# Eth-Crystal.net
KiCad netlist of a schematic drawn in Altium Designer
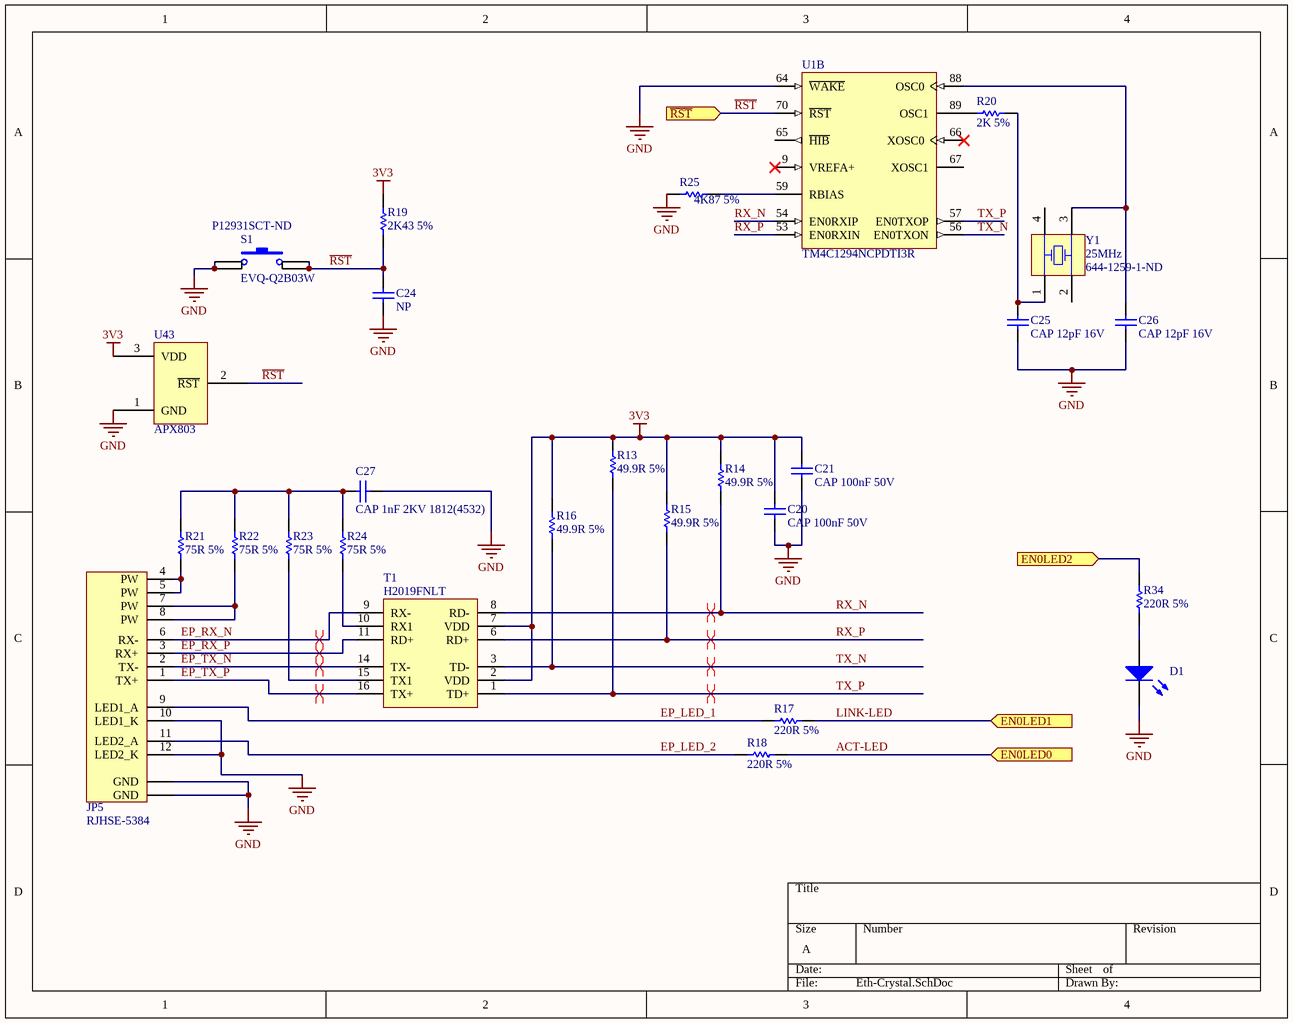
[diagram p0: Eth-Crystal.SchDoc]

(export (version "E")
  (design (tool "Eeschema 10.0.6"))
  (components
    (comp (ref "C20")
      (value "CAP 100nF 50V")
      (footprint "CAPC0603(1608)100_M")
      (description "CAP 100nF 50V Â±0.1pF 0603 (1608 Metric) Thickness 1mm SMD")
      (fields (field (name "TOLERANCE") "Â±0.1pF"))
      (libsource (lib "Altium Content Vault") (part "CMP-1035-00010-1"))
    )
    (comp (ref "C21")
      (value "CAP 100nF 50V")
      (footprint "CAPC0603(1608)100_M")
      (description "CAP 100nF 50V Â±0.1pF 0603 (1608 Metric) Thickness 1mm SMD")
      (fields (field (name "TOLERANCE") "Â±0.1pF"))
      (libsource (lib "Altium Content Vault") (part "CMP-1035-00010-1"))
    )
    (comp (ref "C24")
      (value "NP")
      (footprint "0603")
      (description "Capacitor (Semiconductor SIM Model)")
      (fields (field (name "PUBLISHER") "Altium Limited"))
      (libsource (lib "snarc+") (part "Cap_100pF"))
    )
    (comp (ref "C25")
      (value "CAP 12pF 16V")
      (footprint "CAPC0603(1608)100_L")
      (description "CAP 12pF 16V Â±0.25pF 0603 (1608 Metric) Thickness 1mm SMD")
      (fields (field (name "TOLERANCE") "Â±0.25pF"))
      (libsource (lib "Altium Content Vault") (part "CAP"))
    )
    (comp (ref "C26")
      (value "CAP 12pF 16V")
      (footprint "CAPC0603(1608)100_L")
      (description "CAP 12pF 16V Â±0.25pF 0603 (1608 Metric) Thickness 1mm SMD")
      (fields (field (name "TOLERANCE") "Â±0.25pF"))
      (libsource (lib "Altium Content Vault") (part "CAP"))
    )
    (comp (ref "C27")
      (value "CAP 1nF 2KV 1812(4532)")
      (footprint "CAPC1812(4532)230_N")
      (description "CAP 1nF 2KV Â±10% 1812 (4532 Metric) Thickness 2.3mm SMD")
      (fields (field (name "TOLERANCE") "Â±10%"))
      (libsource (lib "Altium Content Vault") (part "CAP"))
    )
    (comp (ref "D1")
      (value "LED")
      (footprint "LED-0603")
      (description "Typical RED, GREEN, YELLOW, AMBER GaAs LED")
      (fields (field (name "PUBLISHER") "Altium Limited"))
      (libsource (lib "HSBNE-Vend") (part "LED"))
    )
    (comp (ref "JP5")
      (value "RJHSE-5384")
      (footprint "RJHSE-5484")
      (description "Ethernet Socket RJ45 With Leds")
      (libsource (lib "snarc+") (part "Ethernet Socket"))
    )
    (comp (ref "R13")
      (value "49.9R 5%")
      (footprint "RESC0603(1608)_M")
      (description "49.9R 0.1W 5% 0603 (1608 Metric)  SMD")
      (fields (field (name "TOLERANCE") "5 %") (field (name "POWER") "0.1 W"))
      (libsource (lib "Altium Content Vault") (part "CMP-1012-00042-1"))
    )
    (comp (ref "R14")
      (value "49.9R 5%")
      (footprint "RESC0603(1608)_M")
      (description "49.9R 0.1W 5% 0603 (1608 Metric)  SMD")
      (fields (field (name "TOLERANCE") "5 %") (field (name "POWER") "0.1 W"))
      (libsource (lib "Altium Content Vault") (part "CMP-1012-00042-1"))
    )
    (comp (ref "R15")
      (value "49.9R 5%")
      (footprint "RESC0603(1608)_M")
      (description "49.9R 0.1W 5% 0603 (1608 Metric)  SMD")
      (fields (field (name "TOLERANCE") "5 %") (field (name "POWER") "0.1 W"))
      (libsource (lib "Altium Content Vault") (part "CMP-1012-00042-1"))
    )
    (comp (ref "R16")
      (value "49.9R 5%")
      (footprint "RESC0603(1608)_M")
      (description "49.9R 0.1W 5% 0603 (1608 Metric)  SMD")
      (fields (field (name "TOLERANCE") "5 %") (field (name "POWER") "0.1 W"))
      (libsource (lib "Altium Content Vault") (part "CMP-1012-00042-1"))
    )
    (comp (ref "R17")
      (value "220R 5%")
      (footprint "RESC0603(1608)_M")
      (description "220R 0.1W 5% 0603 (1608 Metric)  SMD")
      (fields (field (name "POWER") "0.1 W") (field (name "TOLERANCE") "5 %"))
      (libsource (lib "Altium Content Vault") (part "CMP-1012-00058-1"))
    )
    (comp (ref "R18")
      (value "220R 5%")
      (footprint "RESC0603(1608)_M")
      (description "220R 0.1W 5% 0603 (1608 Metric)  SMD")
      (fields (field (name "POWER") "0.1 W") (field (name "TOLERANCE") "5 %"))
      (libsource (lib "Altium Content Vault") (part "CMP-1012-00058-1"))
    )
    (comp (ref "R19")
      (value "2K43 5%")
      (footprint "RESC0603(1608)_M")
      (description "2K43 0.1W 5% 0603 (1608 Metric)  SMD")
      (fields (field (name "TOLERANCE") "5 %") (field (name "POWER") "0.1 W"))
      (libsource (lib "Altium Content Vault") (part "CMP-1012-00083-1"))
    )
    (comp (ref "R20")
      (value "2K 5%")
      (footprint "RESC0603(1608)_N")
      (description "2K 0.1W 5% 0603 (1608 Metric)  SMD")
      (fields (field (name "TOLERANCE") "5 %") (field (name "POWER") "0.1 W"))
      (libsource (lib "Altium Content Vault") (part "RES"))
    )
    (comp (ref "R21")
      (value "75R 5%")
      (footprint "RESC0603(1608)_N")
      (description "75R 0.1W 5% 0603 (1608 Metric)  SMD")
      (fields (field (name "TOLERANCE") "5 %") (field (name "POWER") "0.1 W"))
      (libsource (lib "Altium Content Vault") (part "CMP-1012-00047-1"))
    )
    (comp (ref "R22")
      (value "75R 5%")
      (footprint "RESC0603(1608)_N")
      (description "75R 0.1W 5% 0603 (1608 Metric)  SMD")
      (fields (field (name "TOLERANCE") "5 %") (field (name "POWER") "0.1 W"))
      (libsource (lib "Altium Content Vault") (part "CMP-1012-00047-1"))
    )
    (comp (ref "R23")
      (value "75R 5%")
      (footprint "RESC0603(1608)_N")
      (description "75R 0.1W 5% 0603 (1608 Metric)  SMD")
      (fields (field (name "TOLERANCE") "5 %") (field (name "POWER") "0.1 W"))
      (libsource (lib "Altium Content Vault") (part "CMP-1012-00047-1"))
    )
    (comp (ref "R24")
      (value "75R 5%")
      (footprint "RESC0603(1608)_N")
      (description "75R 0.1W 5% 0603 (1608 Metric)  SMD")
      (fields (field (name "TOLERANCE") "5 %") (field (name "POWER") "0.1 W"))
      (libsource (lib "Altium Content Vault") (part "CMP-1012-00047-1"))
    )
    (comp (ref "R25")
      (value "4K87 5%")
      (footprint "RESC0603(1608)_M")
      (description "4K87 0.1W 5% 0603 (1608 Metric)  SMD")
      (fields (field (name "TOLERANCE") "5 %") (field (name "POWER") "0.1 W"))
      (libsource (lib "Altium Content Vault") (part "CMP-1012-00090-1"))
    )
    (comp (ref "R34")
      (value "220R 5%")
      (footprint "RESC0603(1608)_M")
      (description "220R 0.1W 5% 0603 (1608 Metric)  SMD")
      (fields (field (name "POWER") "0.1 W") (field (name "TOLERANCE") "5 %"))
      (libsource (lib "Altium Content Vault") (part "CMP-1012-00058-1"))
    )
    (comp (ref "S1")
      (value "EVQ-Q2B03W")
      (footprint "TACTILE_SWITCH_SMD")
      (description "Switch")
      (fields
        (field (name "SUPPLIER PART NUMBER 1") "P12931SCT-ND")
        (field (name "PUBLISHER") "Altium Limited")
      )
      (libsource (lib "snarc+") (part "SW-PB"))
    )
    (comp (ref "T1")
      (value "H2019FNLT")
      (footprint "HXXXX")
      (description "Power over Ethernet Magnetic Module")
      (fields (field (name "PUBLISHER") "Altium Limited"))
      (libsource (lib "snarc+3") (part "Magnetics"))
    )
    (comp (ref "U1")
      (value "TM4C1294NCPDTI3R")
      (footprint "TI-PDT128_M")
      (fields (field (name "MANUFACTURER") "Texas Instruments"))
      (libsource (lib "Altium Inc") (part "TI-TM4C1294NCPDT-128"))
    )
    (comp (ref "U43")
      (value "APX803")
      (footprint "SOT-23 - ESD")
      (description "IC MPU RESET CIRC 3.08V SOT23R-3")
      (libsource (lib "HSBNE-Vend") (part "APX803"))
    )
    (comp (ref "Y1")
      (value "25MHz")
      (footprint "Crystal 3.2x2.5")
      (description "Surface Mount Quartz Crystal")
      (fields
        (field (name "SUPPLIER PART NUMBER 1") "644-1259-1-ND")
        (field (name "PUBLISHER") "Altium Limited")
      )
      (libsource (lib "HSBNE-Vend") (part "Crystal_25MHz"))
    )
  )
  (nets
    (net (code "1") (name "/ACT-LED") (class "Default")
      (node (ref "R18") (pin "2") (pinfunction "2_2") (pintype "passive"))
    )
    (net (code "2") (name "/EN0LED2") (class "Default")
      (node (ref "R34") (pin "2") (pinfunction "2_2") (pintype "passive"))
    )
    (net (code "3") (name "/EP_LED_1") (class "Default")
      (node (ref "JP5") (pin "9") (pinfunction "LED1_A_9") (pintype "passive"))
      (node (ref "R17") (pin "1") (pinfunction "1_1") (pintype "passive"))
    )
    (net (code "4") (name "/EP_LED_2") (class "Default")
      (node (ref "JP5") (pin "11") (pinfunction "LED2_A_11") (pintype "passive"))
      (node (ref "R18") (pin "1") (pinfunction "1_1") (pintype "passive"))
    )
    (net (code "5") (name "/EP_RX_N") (class "Default")
      (node (ref "JP5") (pin "6") (pinfunction "RX-_6") (pintype "passive"))
      (node (ref "T1") (pin "9") (pinfunction "RX-_9") (pintype "passive"))
    )
    (net (code "6") (name "/EP_RX_P") (class "Default")
      (node (ref "JP5") (pin "3") (pinfunction "RX+_3") (pintype "passive"))
      (node (ref "T1") (pin "11") (pinfunction "RD+_11") (pintype "passive"))
    )
    (net (code "7") (name "/EP_TX_N") (class "Default")
      (node (ref "JP5") (pin "2") (pinfunction "TX-_2") (pintype "passive"))
      (node (ref "T1") (pin "14") (pinfunction "TX-_14") (pintype "passive"))
    )
    (net (code "8") (name "/EP_TX_P") (class "Default")
      (node (ref "JP5") (pin "1") (pinfunction "TX+_1") (pintype "passive"))
      (node (ref "T1") (pin "16") (pinfunction "TX+_16") (pintype "passive"))
    )
    (net (code "9") (name "/LINK-LED") (class "Default")
      (node (ref "R17") (pin "2") (pinfunction "2_2") (pintype "passive"))
    )
    (net (code "10") (name "/RX_N") (class "Default")
      (node (ref "R14") (pin "1") (pinfunction "1_1") (pintype "passive"))
      (node (ref "T1") (pin "8") (pinfunction "RD-_8") (pintype "passive"))
      (node (ref "U1") (pin "54") (pinfunction "EN0RXIP_54") (pintype "input"))
    )
    (net (code "11") (name "/RX_P") (class "Default")
      (node (ref "R15") (pin "1") (pinfunction "1_1") (pintype "passive"))
      (node (ref "T1") (pin "6") (pinfunction "RD+_6") (pintype "passive"))
      (node (ref "U1") (pin "53") (pinfunction "EN0RXIN_53") (pintype "input"))
    )
    (net (code "12") (name "/TX_N") (class "Default")
      (node (ref "R16") (pin "1") (pinfunction "1_1") (pintype "passive"))
      (node (ref "T1") (pin "3") (pinfunction "TD-_3") (pintype "passive"))
      (node (ref "U1") (pin "56") (pinfunction "EN0TXON_56") (pintype "output"))
    )
    (net (code "13") (name "/TX_P") (class "Default")
      (node (ref "R13") (pin "1") (pinfunction "1_1") (pintype "passive"))
      (node (ref "T1") (pin "1") (pinfunction "TD+_1") (pintype "passive"))
      (node (ref "U1") (pin "57") (pinfunction "EN0TXOP_57") (pintype "output"))
    )
    (net (code "14") (name "/~{RST}") (class "Default")
      (node (ref "C24") (pin "2") (pinfunction "2_2") (pintype "passive"))
      (node (ref "R19") (pin "1") (pinfunction "1_1") (pintype "passive"))
      (node (ref "S1") (pin "3") (pinfunction "3_3") (pintype "passive"))
      (node (ref "S1") (pin "4") (pinfunction "4_4") (pintype "passive"))
      (node (ref "U1") (pin "70") (pinfunction "~{RST}_70") (pintype "input"))
      (node (ref "U43") (pin "2") (pinfunction "~{RST}_2") (pintype "passive"))
    )
    (net (code "15") (name "3V3") (class "Default")
      (node (ref "C20") (pin "2") (pinfunction "2_2") (pintype "passive"))
      (node (ref "C21") (pin "2") (pinfunction "2_2") (pintype "passive"))
      (node (ref "R13") (pin "2") (pinfunction "2_2") (pintype "passive"))
      (node (ref "R14") (pin "2") (pinfunction "2_2") (pintype "passive"))
      (node (ref "R15") (pin "2") (pinfunction "2_2") (pintype "passive"))
      (node (ref "R16") (pin "2") (pinfunction "2_2") (pintype "passive"))
      (node (ref "R19") (pin "2") (pinfunction "2_2") (pintype "passive"))
      (node (ref "T1") (pin "2") (pinfunction "VDD_2") (pintype "passive"))
      (node (ref "T1") (pin "7") (pinfunction "VDD_7") (pintype "passive"))
      (node (ref "U43") (pin "3") (pinfunction "VDD_3") (pintype "passive"))
    )
    (net (code "16") (name "GND") (class "Default")
      (node (ref "C20") (pin "1") (pinfunction "1_1") (pintype "passive"))
      (node (ref "C21") (pin "1") (pinfunction "1_1") (pintype "passive"))
      (node (ref "C24") (pin "1") (pinfunction "1_1") (pintype "passive"))
      (node (ref "C25") (pin "1") (pinfunction "1_1") (pintype "passive"))
      (node (ref "C26") (pin "1") (pinfunction "1_1") (pintype "passive"))
      (node (ref "C27") (pin "2") (pinfunction "2_2") (pintype "passive"))
      (node (ref "D1") (pin "2") (pinfunction "K_2") (pintype "passive"))
      (node (ref "JP5") (pin "10") (pinfunction "LED1_K_10") (pintype "passive"))
      (node (ref "JP5") (pin "12") (pinfunction "LED2_K_12") (pintype "passive"))
      (node (ref "JP5") (pin "GND1") (pinfunction "GND_GND1") (pintype "passive"))
      (node (ref "JP5") (pin "GND2") (pinfunction "GND_GND2") (pintype "passive"))
      (node (ref "R25") (pin "1") (pinfunction "1_1") (pintype "passive"))
      (node (ref "S1") (pin "1") (pinfunction "1_1") (pintype "passive"))
      (node (ref "S1") (pin "2") (pinfunction "2_2") (pintype "passive"))
      (node (ref "U1") (pin "64") (pinfunction "~{WAKE}_64") (pintype "input"))
      (node (ref "U43") (pin "1") (pinfunction "GND_1") (pintype "passive"))
    )
    (net (code "17") (name "Net-(C25-Pad2)") (class "Default")
      (node (ref "C25") (pin "2") (pinfunction "2_2") (pintype "passive"))
      (node (ref "R20") (pin "2") (pinfunction "2_2") (pintype "passive"))
      (node (ref "Y1") (pin "1") (pinfunction "OSC1_1") (pintype "passive"))
    )
    (net (code "18") (name "Net-(C27-Pad1)") (class "Default")
      (node (ref "C27") (pin "1") (pinfunction "1_1") (pintype "passive"))
      (node (ref "R21") (pin "2") (pinfunction "2_2") (pintype "passive"))
      (node (ref "R22") (pin "2") (pinfunction "2_2") (pintype "passive"))
      (node (ref "R23") (pin "2") (pinfunction "2_2") (pintype "passive"))
      (node (ref "R24") (pin "2") (pinfunction "2_2") (pintype "passive"))
    )
    (net (code "19") (name "Net-(D1-A)") (class "Default")
      (node (ref "D1") (pin "1") (pinfunction "A_1") (pintype "passive"))
      (node (ref "R34") (pin "1") (pinfunction "1_1") (pintype "passive"))
    )
    (net (code "20") (name "Net-(JP5-PW-Pad4)") (class "Default")
      (node (ref "JP5") (pin "4") (pinfunction "PW_4") (pintype "passive"))
      (node (ref "JP5") (pin "5") (pinfunction "PW_5") (pintype "passive"))
      (node (ref "R21") (pin "1") (pinfunction "1_1") (pintype "passive"))
    )
    (net (code "21") (name "Net-(JP5-PW-Pad7)") (class "Default")
      (node (ref "JP5") (pin "7") (pinfunction "PW_7") (pintype "passive"))
      (node (ref "JP5") (pin "8") (pinfunction "PW_8") (pintype "passive"))
      (node (ref "R22") (pin "1") (pinfunction "1_1") (pintype "passive"))
    )
    (net (code "22") (name "Net-(T1-RX1)") (class "Default")
      (node (ref "R24") (pin "1") (pinfunction "1_1") (pintype "passive"))
      (node (ref "T1") (pin "10") (pinfunction "RX1_10") (pintype "passive"))
    )
    (net (code "23") (name "Net-(T1-TX1)") (class "Default")
      (node (ref "R23") (pin "1") (pinfunction "1_1") (pintype "passive"))
      (node (ref "T1") (pin "15") (pinfunction "TX1_15") (pintype "passive"))
    )
    (net (code "24") (name "Net-(U1B-OSC0)") (class "Default")
      (node (ref "C26") (pin "2") (pinfunction "2_2") (pintype "passive"))
      (node (ref "U1") (pin "88") (pinfunction "OSC0_88") (pintype "input"))
      (node (ref "Y1") (pin "3") (pinfunction "OSC2_3") (pintype "passive"))
    )
    (net (code "25") (name "Net-(U1B-OSC1)") (class "Default")
      (node (ref "R20") (pin "1") (pinfunction "1_1") (pintype "passive"))
      (node (ref "U1") (pin "89") (pinfunction "OSC1_89") (pintype "passive"))
    )
    (net (code "26") (name "Net-(U1B-RBIAS)") (class "Default")
      (node (ref "R25") (pin "2") (pinfunction "2_2") (pintype "passive"))
      (node (ref "U1") (pin "59") (pinfunction "RBIAS_59") (pintype "passive"))
    )
    (net (code "27") (name "unconnected-(U1B-VREFA+-Pad9)") (class "Default")
      (node (ref "U1") (pin "9") (pinfunction "VREFA+_9") (pintype "input+no_connect"))
    )
    (net (code "28") (name "unconnected-(U1B-XOSC0-Pad66)") (class "Default")
      (node (ref "U1") (pin "66") (pinfunction "XOSC0_66") (pintype "input+no_connect"))
    )
    (net (code "29") (name "unconnected-(U1B-XOSC1-Pad67)") (class "Default")
      (node (ref "U1") (pin "67") (pinfunction "XOSC1_67") (pintype "passive"))
    )
    (net (code "30") (name "unconnected-(U1B-~{HIB}-Pad65)") (class "Default")
      (node (ref "U1") (pin "65") (pinfunction "~{HIB}_65") (pintype "output"))
    )
    (net (code "31") (name "unconnected-(Y1-OSC1-Pad4)") (class "Default")
      (node (ref "Y1") (pin "4") (pinfunction "OSC1_4") (pintype "passive"))
    )
    (net (code "32") (name "unconnected-(Y1-OSC2-Pad2)") (class "Default")
      (node (ref "Y1") (pin "2") (pinfunction "OSC2_2") (pintype "passive"))
    )
  )
)
